# PuckerUpVibe.net
KiCad netlist of a schematic drawn in EAGLE
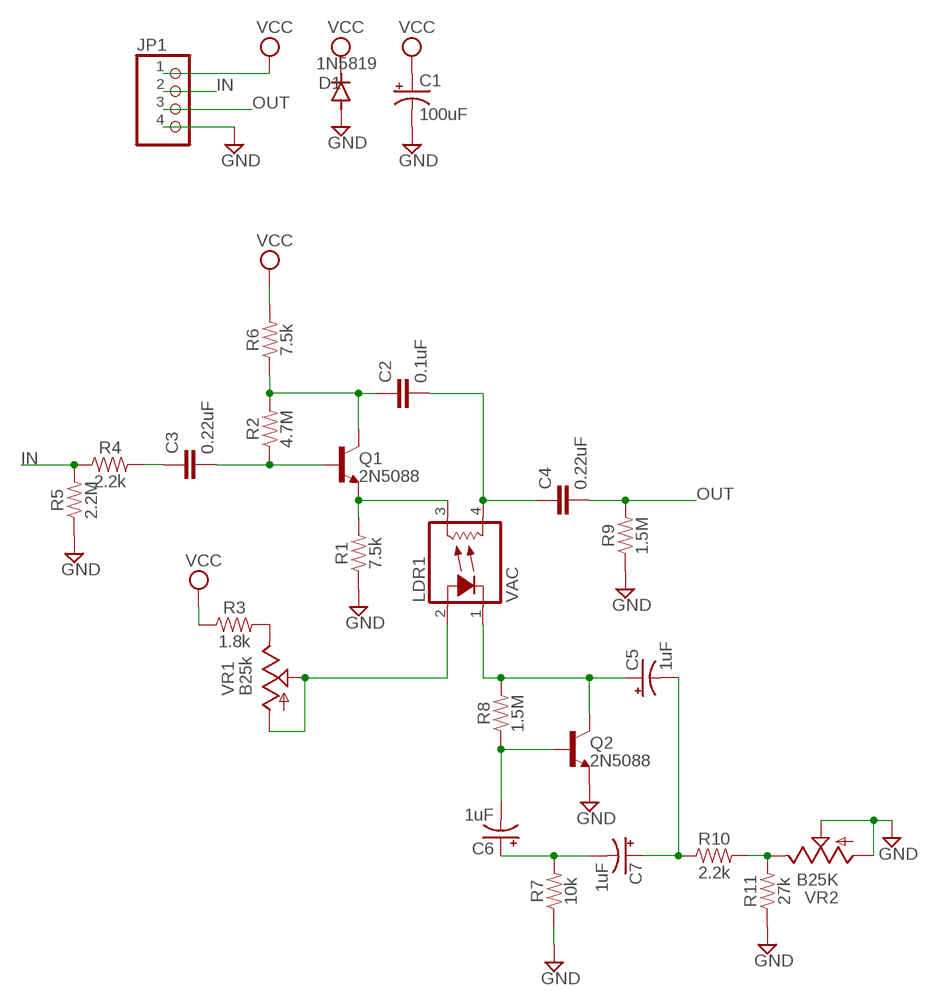
[diagram p0: schematic, sheet 1]

(export (version "E")
  (design (tool "Eeschema 10.0.6"))
  (components
    (comp (ref "C1")
      (value "100uF")
      (footprint "eagle-import:PAN_B_SMD+THRU")
      (libsource (lib "eagle-import") (part "CAP_SMD+THRUPAN_B"))
    )
    (comp (ref "C2")
      (value "0.1uF")
      (footprint "eagle-import:0603")
      (libsource (lib "eagle-import") (part "0.1UF-0603-25V-(+80/-20%)"))
    )
    (comp (ref "C3")
      (value "0.22uF")
      (footprint "eagle-import:0603")
      (libsource (lib "eagle-import") (part "0.22UF-0603-25V-10%"))
    )
    (comp (ref "C4")
      (value "0.22uF")
      (footprint "eagle-import:0603")
      (libsource (lib "eagle-import") (part "0.22UF-0603-25V-10%"))
    )
    (comp (ref "C5")
      (value "1uF")
      (footprint "eagle-import:PAN_B_SMD+THRU")
      (libsource (lib "eagle-import") (part "CAP_SMD+THRUPAN_B"))
    )
    (comp (ref "C6")
      (value "1uF")
      (footprint "eagle-import:PAN_B_SMD+THRU")
      (libsource (lib "eagle-import") (part "CAP_SMD+THRUPAN_B"))
    )
    (comp (ref "C7")
      (value "1uF")
      (footprint "eagle-import:PAN_B_SMD+THRU")
      (libsource (lib "eagle-import") (part "CAP_SMD+THRUPAN_B"))
    )
    (comp (ref "D1")
      (value "1N5819")
      (footprint "eagle-import:SOD123")
      (libsource (lib "eagle-import") (part "DIODE-SOD123"))
    )
    (comp (ref "JP1")
      (value "PINHD-1X4")
      (footprint "eagle-import:1X04")
      (libsource (lib "eagle-import") (part "PINHD-1X4"))
    )
    (comp (ref "LDR1")
      (value "VAC")
      (footprint "eagle-import:VACTROL_4PIN_VTL5C")
      (libsource (lib "eagle-import") (part "VACTROL_4PIN"))
    )
    (comp (ref "Q1")
      (value "2N5088")
      (footprint "eagle-import:TO92-")
      (libsource (lib "eagle-import") (part "2N5088"))
    )
    (comp (ref "Q2")
      (value "2N5088")
      (footprint "eagle-import:TO92-")
      (libsource (lib "eagle-import") (part "2N5088"))
    )
    (comp (ref "R1")
      (value "7.5k")
      (footprint "eagle-import:0603")
      (libsource (lib "eagle-import") (part "RESISTOR0603"))
    )
    (comp (ref "R2")
      (value "4.7M")
      (footprint "eagle-import:0603")
      (libsource (lib "eagle-import") (part "RESISTOR0603"))
    )
    (comp (ref "R3")
      (value "1.8k")
      (footprint "eagle-import:0603")
      (libsource (lib "eagle-import") (part "RESISTOR0603"))
    )
    (comp (ref "R4")
      (value "2.2k")
      (footprint "eagle-import:0603")
      (libsource (lib "eagle-import") (part "RESISTOR0603"))
    )
    (comp (ref "R5")
      (value "2.2M")
      (footprint "eagle-import:0603")
      (libsource (lib "eagle-import") (part "RESISTOR0603"))
    )
    (comp (ref "R6")
      (value "7.5k")
      (footprint "eagle-import:0603")
      (libsource (lib "eagle-import") (part "RESISTOR0603"))
    )
    (comp (ref "R7")
      (value "10k")
      (footprint "eagle-import:0603")
      (libsource (lib "eagle-import") (part "RESISTOR0603"))
    )
    (comp (ref "R8")
      (value "1.5M")
      (footprint "eagle-import:0603")
      (libsource (lib "eagle-import") (part "RESISTOR0603"))
    )
    (comp (ref "R9")
      (value "1.5M")
      (footprint "eagle-import:0603")
      (libsource (lib "eagle-import") (part "RESISTOR0603"))
    )
    (comp (ref "R10")
      (value "2.2k")
      (footprint "eagle-import:0603")
      (libsource (lib "eagle-import") (part "RESISTOR0603"))
    )
    (comp (ref "R11")
      (value "27k")
      (footprint "eagle-import:0603")
      (libsource (lib "eagle-import") (part "RESISTOR0603"))
    )
    (comp (ref "VR1")
      (value "B25k")
      (footprint "eagle-import:9MM_SNAP-IN_POT")
      (libsource (lib "eagle-import") (part "9MM_SNAP-IN_POT_"))
    )
    (comp (ref "VR2")
      (value "B25K")
      (footprint "eagle-import:9MM_SNAP-IN_POT")
      (libsource (lib "eagle-import") (part "9MM_SNAP-IN_POT_"))
    )
  )
  (nets
    (net (code "1") (name "/IN") (class "Default")
      (node (ref "JP1") (pin "2") (pinfunction "2_2") (pintype "passive"))
      (node (ref "R4") (pin "1") (pinfunction "1_1") (pintype "passive"))
      (node (ref "R5") (pin "2") (pinfunction "2_2") (pintype "passive"))
    )
    (net (code "2") (name "/OUT") (class "Default")
      (node (ref "C4") (pin "2") (pinfunction "2_2") (pintype "passive"))
      (node (ref "JP1") (pin "3") (pinfunction "3_3") (pintype "passive"))
      (node (ref "R9") (pin "2") (pinfunction "2_2") (pintype "passive"))
    )
    (net (code "3") (name "GND") (class "Default")
      (node (ref "C1") (pin "-") (pinfunction "-_-") (pintype "passive"))
      (node (ref "C1") (pin "--") (pinfunction "-_--") (pintype "passive"))
      (node (ref "D1") (pin "A") (pinfunction "A_A") (pintype "passive"))
      (node (ref "JP1") (pin "4") (pinfunction "4_4") (pintype "passive"))
      (node (ref "Q2") (pin "3") (pinfunction "E_3") (pintype "passive"))
      (node (ref "R1") (pin "1") (pinfunction "1_1") (pintype "passive"))
      (node (ref "R11") (pin "1") (pinfunction "1_1") (pintype "passive"))
      (node (ref "R5") (pin "1") (pinfunction "1_1") (pintype "passive"))
      (node (ref "R7") (pin "1") (pinfunction "1_1") (pintype "passive"))
      (node (ref "R9") (pin "1") (pinfunction "1_1") (pintype "passive"))
      (node (ref "VR2") (pin "1") (pinfunction "A_1") (pintype "passive"))
      (node (ref "VR2") (pin "2") (pinfunction "S_2") (pintype "passive"))
    )
    (net (code "4") (name "Net-(C3-Pad1)") (class "Default")
      (node (ref "C3") (pin "1") (pinfunction "1_1") (pintype "passive"))
      (node (ref "R4") (pin "2") (pinfunction "2_2") (pintype "passive"))
    )
    (net (code "5") (name "Net-(C5---Pad--)") (class "Default")
      (node (ref "C5") (pin "-") (pinfunction "-_-") (pintype "passive"))
      (node (ref "C5") (pin "--") (pinfunction "-_--") (pintype "passive"))
      (node (ref "C7") (pin "+") (pinfunction "+_+") (pintype "passive"))
      (node (ref "C7") (pin "++") (pinfunction "+_++") (pintype "passive"))
      (node (ref "R10") (pin "1") (pinfunction "1_1") (pintype "passive"))
    )
    (net (code "6") (name "Net-(C6-+-Pad++)") (class "Default")
      (node (ref "C6") (pin "+") (pinfunction "+_+") (pintype "passive"))
      (node (ref "C6") (pin "++") (pinfunction "+_++") (pintype "passive"))
      (node (ref "C7") (pin "-") (pinfunction "-_-") (pintype "passive"))
      (node (ref "C7") (pin "--") (pinfunction "-_--") (pintype "passive"))
      (node (ref "R7") (pin "2") (pinfunction "2_2") (pintype "passive"))
    )
    (net (code "7") (name "Net-(LDR1-LED+)") (class "Default")
      (node (ref "LDR1") (pin "2") (pinfunction "LED+_2") (pintype "passive"))
      (node (ref "VR1") (pin "1") (pinfunction "A_1") (pintype "passive"))
      (node (ref "VR1") (pin "2") (pinfunction "S_2") (pintype "passive"))
    )
    (net (code "8") (name "Net-(LDR1-LED-)") (class "Default")
      (node (ref "C5") (pin "+") (pinfunction "+_+") (pintype "passive"))
      (node (ref "C5") (pin "++") (pinfunction "+_++") (pintype "passive"))
      (node (ref "LDR1") (pin "1") (pinfunction "LED-_1") (pintype "passive"))
      (node (ref "Q2") (pin "1") (pinfunction "C_1") (pintype "passive"))
      (node (ref "R8") (pin "2") (pinfunction "2_2") (pintype "passive"))
    )
    (net (code "9") (name "Net-(LDR1-RES1)") (class "Default")
      (node (ref "LDR1") (pin "3") (pinfunction "RES1_3") (pintype "passive"))
      (node (ref "Q1") (pin "3") (pinfunction "E_3") (pintype "passive"))
      (node (ref "R1") (pin "2") (pinfunction "2_2") (pintype "passive"))
    )
    (net (code "10") (name "Net-(LDR1-RES2)") (class "Default")
      (node (ref "C2") (pin "2") (pinfunction "2_2") (pintype "passive"))
      (node (ref "C4") (pin "1") (pinfunction "1_1") (pintype "passive"))
      (node (ref "LDR1") (pin "4") (pinfunction "RES2_4") (pintype "passive"))
    )
    (net (code "11") (name "Net-(Q1-B)") (class "Default")
      (node (ref "C3") (pin "2") (pinfunction "2_2") (pintype "passive"))
      (node (ref "Q1") (pin "2") (pinfunction "B_2") (pintype "passive"))
      (node (ref "R2") (pin "1") (pinfunction "1_1") (pintype "passive"))
    )
    (net (code "12") (name "Net-(Q1-C)") (class "Default")
      (node (ref "C2") (pin "1") (pinfunction "1_1") (pintype "passive"))
      (node (ref "Q1") (pin "1") (pinfunction "C_1") (pintype "passive"))
      (node (ref "R2") (pin "2") (pinfunction "2_2") (pintype "passive"))
      (node (ref "R6") (pin "1") (pinfunction "1_1") (pintype "passive"))
    )
    (net (code "13") (name "Net-(Q2-B)") (class "Default")
      (node (ref "C6") (pin "-") (pinfunction "-_-") (pintype "passive"))
      (node (ref "C6") (pin "--") (pinfunction "-_--") (pintype "passive"))
      (node (ref "Q2") (pin "2") (pinfunction "B_2") (pintype "passive"))
      (node (ref "R8") (pin "1") (pinfunction "1_1") (pintype "passive"))
    )
    (net (code "14") (name "Net-(VR1-E)") (class "Default")
      (node (ref "R3") (pin "2") (pinfunction "2_2") (pintype "passive"))
      (node (ref "VR1") (pin "3") (pinfunction "E_3") (pintype "passive"))
    )
    (net (code "15") (name "Net-(VR2-E)") (class "Default")
      (node (ref "R10") (pin "2") (pinfunction "2_2") (pintype "passive"))
      (node (ref "R11") (pin "2") (pinfunction "2_2") (pintype "passive"))
      (node (ref "VR2") (pin "3") (pinfunction "E_3") (pintype "passive"))
    )
    (net (code "16") (name "VCC") (class "Default")
      (node (ref "C1") (pin "+") (pinfunction "+_+") (pintype "passive"))
      (node (ref "C1") (pin "++") (pinfunction "+_++") (pintype "passive"))
      (node (ref "D1") (pin "C") (pinfunction "C_C") (pintype "passive"))
      (node (ref "JP1") (pin "1") (pinfunction "1_1") (pintype "passive"))
      (node (ref "R3") (pin "1") (pinfunction "1_1") (pintype "passive"))
      (node (ref "R6") (pin "2") (pinfunction "2_2") (pintype "passive"))
    )
  )
)
